# EFM32TG110_BreakoutBoard.net
KiCad netlist of a schematic drawn in EAGLE
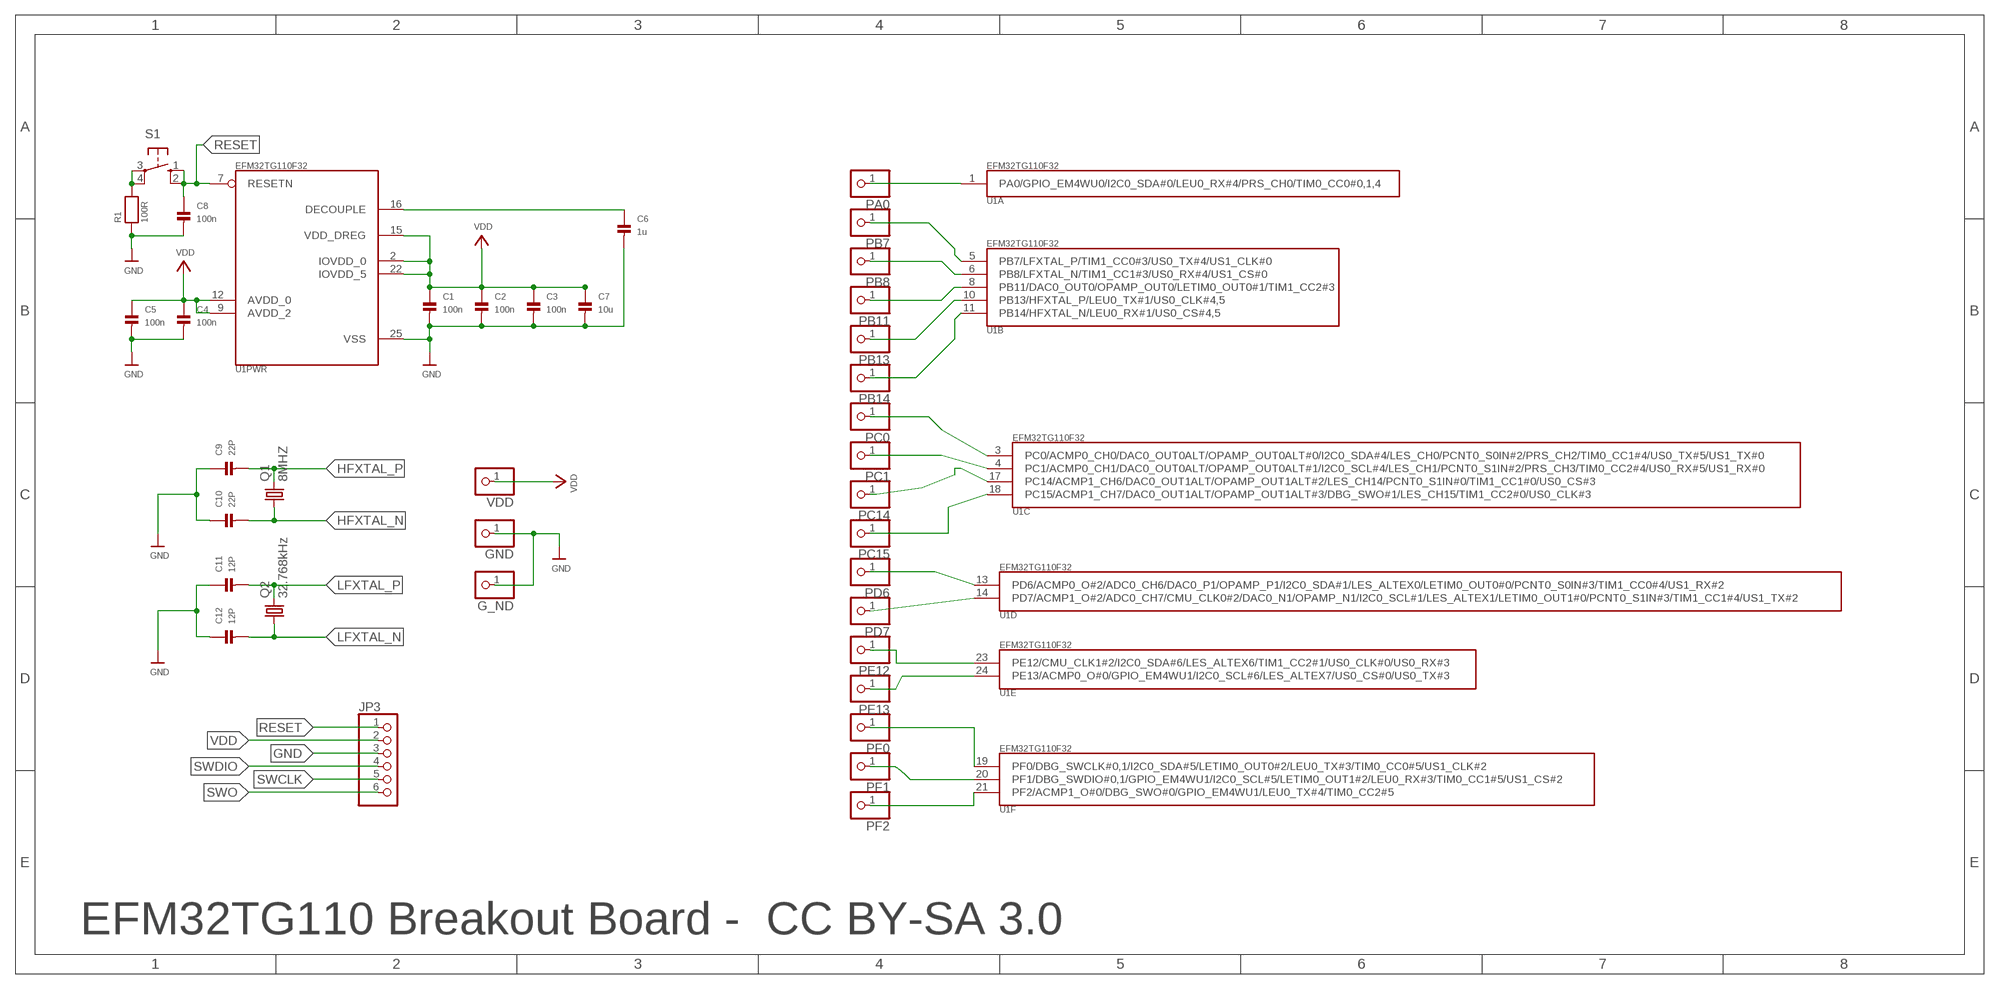
[diagram p0: schematic, sheet 1]

(export (version "E")
  (design (tool "Eeschema 10.0.6"))
  (components
    (comp (ref "C1")
      (value "100n")
      (footprint "eagle-import:0603")
      (libsource (lib "eagle-import") (part "CAP_CERAMIC0603"))
    )
    (comp (ref "C2")
      (value "100n")
      (footprint "eagle-import:0603")
      (libsource (lib "eagle-import") (part "CAP_CERAMIC0603"))
    )
    (comp (ref "C3")
      (value "100n")
      (footprint "eagle-import:0603")
      (libsource (lib "eagle-import") (part "CAP_CERAMIC0603"))
    )
    (comp (ref "C4")
      (value "100n")
      (footprint "eagle-import:0603")
      (libsource (lib "eagle-import") (part "CAP_CERAMIC0603"))
    )
    (comp (ref "C5")
      (value "100n")
      (footprint "eagle-import:0603")
      (libsource (lib "eagle-import") (part "CAP_CERAMIC0603"))
    )
    (comp (ref "C6")
      (value "1u")
      (footprint "eagle-import:0805")
      (libsource (lib "eagle-import") (part "CAP_CERAMIC0805"))
    )
    (comp (ref "C7")
      (value "10u")
      (footprint "eagle-import:0805")
      (libsource (lib "eagle-import") (part "CAP_CERAMIC0805"))
    )
    (comp (ref "C8")
      (value "100n")
      (footprint "eagle-import:0603")
      (libsource (lib "eagle-import") (part "CAP_CERAMIC0603"))
    )
    (comp (ref "C9")
      (value "22P")
      (footprint "eagle-import:0603")
      (libsource (lib "eagle-import") (part "CAP_CERAMIC0603"))
    )
    (comp (ref "C10")
      (value "22P")
      (footprint "eagle-import:0603")
      (libsource (lib "eagle-import") (part "CAP_CERAMIC0603"))
    )
    (comp (ref "C11")
      (value "12P")
      (footprint "eagle-import:0603")
      (libsource (lib "eagle-import") (part "CAP_CERAMIC0603"))
    )
    (comp (ref "C12")
      (value "12P")
      (footprint "eagle-import:0603")
      (libsource (lib "eagle-import") (part "CAP_CERAMIC0603"))
    )
    (comp (ref "GND")
      (value "HEADER-1X1ROUND")
      (footprint "eagle-import:1X01_ROUND")
      (libsource (lib "eagle-import") (part "HEADER-1X1ROUND"))
    )
    (comp (ref "G_ND")
      (value "HEADER-1X1ROUND")
      (footprint "eagle-import:1X01_ROUND")
      (libsource (lib "eagle-import") (part "HEADER-1X1ROUND"))
    )
    (comp (ref "JP3")
      (value "HEADER-1X6")
      (footprint "eagle-import:1X06_OVAL")
      (libsource (lib "eagle-import") (part "HEADER-1X6"))
    )
    (comp (ref "PA0")
      (value "HEADER-1X1ROUND")
      (footprint "eagle-import:1X01_ROUND")
      (libsource (lib "eagle-import") (part "HEADER-1X1ROUND"))
    )
    (comp (ref "PB7")
      (value "HEADER-1X1ROUND")
      (footprint "eagle-import:1X01_ROUND")
      (libsource (lib "eagle-import") (part "HEADER-1X1ROUND"))
    )
    (comp (ref "PB8")
      (value "HEADER-1X1ROUND")
      (footprint "eagle-import:1X01_ROUND")
      (libsource (lib "eagle-import") (part "HEADER-1X1ROUND"))
    )
    (comp (ref "PB11")
      (value "HEADER-1X1ROUND")
      (footprint "eagle-import:1X01_ROUND")
      (libsource (lib "eagle-import") (part "HEADER-1X1ROUND"))
    )
    (comp (ref "PB13")
      (value "HEADER-1X1ROUND")
      (footprint "eagle-import:1X01_ROUND")
      (libsource (lib "eagle-import") (part "HEADER-1X1ROUND"))
    )
    (comp (ref "PB14")
      (value "HEADER-1X1ROUND")
      (footprint "eagle-import:1X01_ROUND")
      (libsource (lib "eagle-import") (part "HEADER-1X1ROUND"))
    )
    (comp (ref "PC0")
      (value "HEADER-1X1ROUND")
      (footprint "eagle-import:1X01_ROUND")
      (libsource (lib "eagle-import") (part "HEADER-1X1ROUND"))
    )
    (comp (ref "PC1")
      (value "HEADER-1X1ROUND")
      (footprint "eagle-import:1X01_ROUND")
      (libsource (lib "eagle-import") (part "HEADER-1X1ROUND"))
    )
    (comp (ref "PC14")
      (value "HEADER-1X1ROUND")
      (footprint "eagle-import:1X01_ROUND")
      (libsource (lib "eagle-import") (part "HEADER-1X1ROUND"))
    )
    (comp (ref "PC15")
      (value "HEADER-1X1ROUND")
      (footprint "eagle-import:1X01_ROUND")
      (libsource (lib "eagle-import") (part "HEADER-1X1ROUND"))
    )
    (comp (ref "PD6")
      (value "HEADER-1X1ROUND")
      (footprint "eagle-import:1X01_ROUND")
      (libsource (lib "eagle-import") (part "HEADER-1X1ROUND"))
    )
    (comp (ref "PD7")
      (value "HEADER-1X1ROUND")
      (footprint "eagle-import:1X01_ROUND")
      (libsource (lib "eagle-import") (part "HEADER-1X1ROUND"))
    )
    (comp (ref "PE12")
      (value "HEADER-1X1ROUND")
      (footprint "eagle-import:1X01_ROUND")
      (libsource (lib "eagle-import") (part "HEADER-1X1ROUND"))
    )
    (comp (ref "PE13")
      (value "HEADER-1X1ROUND")
      (footprint "eagle-import:1X01_ROUND")
      (libsource (lib "eagle-import") (part "HEADER-1X1ROUND"))
    )
    (comp (ref "PF0")
      (value "HEADER-1X1ROUND")
      (footprint "eagle-import:1X01_ROUND")
      (libsource (lib "eagle-import") (part "HEADER-1X1ROUND"))
    )
    (comp (ref "PF1")
      (value "HEADER-1X1ROUND")
      (footprint "eagle-import:1X01_ROUND")
      (libsource (lib "eagle-import") (part "HEADER-1X1ROUND"))
    )
    (comp (ref "PF2")
      (value "HEADER-1X1ROUND")
      (footprint "eagle-import:1X01_ROUND")
      (libsource (lib "eagle-import") (part "HEADER-1X1ROUND"))
    )
    (comp (ref "Q1")
      (value "8MHZ")
      (footprint "eagle-import:HC49U70")
      (libsource (lib "eagle-import") (part "CRYSTALHC49U70"))
    )
    (comp (ref "Q2")
      (value "32.768kHz")
      (footprint "eagle-import:TC38H")
      (libsource (lib "eagle-import") (part "CRYSTALTC38H"))
    )
    (comp (ref "R1")
      (value "100R")
      (footprint "eagle-import:0603")
      (libsource (lib "eagle-import") (part "RESISTOR0603"))
    )
    (comp (ref "S1")
      (value "10-XX")
      (footprint "eagle-import:B3F-10XX")
      (fields (field (name "MPN") "B3F-1000"))
      (libsource (lib "eagle-import") (part "10-XX"))
    )
    (comp (ref "U1")
      (value "EFM32TG110F32")
      (footprint "eagle-import:QFN24")
      (libsource (lib "eagle-import") (part "EFM32TG110F32"))
    )
    (comp (ref "VDD")
      (value "HEADER-1X1ROUND")
      (footprint "eagle-import:1X01_ROUND")
      (libsource (lib "eagle-import") (part "HEADER-1X1ROUND"))
    )
  )
  (nets
    (net (code "1") (name "GND") (class "Default")
      (node (ref "C1") (pin "2") (pinfunction "P$2_2") (pintype "passive"))
      (node (ref "C10") (pin "1") (pinfunction "P$1_1") (pintype "passive"))
      (node (ref "C11") (pin "1") (pinfunction "P$1_1") (pintype "passive"))
      (node (ref "C12") (pin "1") (pinfunction "P$1_1") (pintype "passive"))
      (node (ref "C2") (pin "2") (pinfunction "P$2_2") (pintype "passive"))
      (node (ref "C3") (pin "2") (pinfunction "P$2_2") (pintype "passive"))
      (node (ref "C4") (pin "2") (pinfunction "P$2_2") (pintype "passive"))
      (node (ref "C5") (pin "2") (pinfunction "P$2_2") (pintype "passive"))
      (node (ref "C6") (pin "2") (pinfunction "P$2_2") (pintype "passive"))
      (node (ref "C7") (pin "2") (pinfunction "P$2_2") (pintype "passive"))
      (node (ref "C8") (pin "2") (pinfunction "P$2_2") (pintype "passive"))
      (node (ref "C9") (pin "1") (pinfunction "P$1_1") (pintype "passive"))
      (node (ref "GND") (pin "1") (pinfunction "1_1") (pintype "passive"))
      (node (ref "G_ND") (pin "1") (pinfunction "1_1") (pintype "passive"))
      (node (ref "JP3") (pin "3") (pinfunction "3_3") (pintype "passive"))
      (node (ref "R1") (pin "1") (pinfunction "1_1") (pintype "passive"))
      (node (ref "U1") (pin "25") (pinfunction "VSS_25") (pintype "power_in"))
    )
    (net (code "2") (name "HFXTAL_N") (class "Default")
      (node (ref "C10") (pin "2") (pinfunction "P$2_2") (pintype "passive"))
      (node (ref "PB14") (pin "1") (pinfunction "1_1") (pintype "passive"))
      (node (ref "Q1") (pin "1") (pinfunction "1_1") (pintype "passive"))
      (node (ref "U1") (pin "11") (pinfunction "PB14/HFXTAL_N/LEU0_RX#1/US0_CS#4,5_11") (pintype "bidirectional"))
    )
    (net (code "3") (name "HFXTAL_P") (class "Default")
      (node (ref "C9") (pin "2") (pinfunction "P$2_2") (pintype "passive"))
      (node (ref "PB13") (pin "1") (pinfunction "1_1") (pintype "passive"))
      (node (ref "Q1") (pin "2") (pinfunction "2_2") (pintype "passive"))
      (node (ref "U1") (pin "10") (pinfunction "PB13/HFXTAL_P/LEU0_TX#1/US0_CLK#4,5_10") (pintype "bidirectional"))
    )
    (net (code "4") (name "LFXTAL_N") (class "Default")
      (node (ref "C12") (pin "2") (pinfunction "P$2_2") (pintype "passive"))
      (node (ref "PB8") (pin "1") (pinfunction "1_1") (pintype "passive"))
      (node (ref "Q2") (pin "1") (pinfunction "1_1") (pintype "passive"))
      (node (ref "U1") (pin "6") (pinfunction "PB8/LFXTAL_N/TIM1_CC1#3/US0_RX#4/US1_CS#0_6") (pintype "bidirectional"))
    )
    (net (code "5") (name "LFXTAL_P") (class "Default")
      (node (ref "C11") (pin "2") (pinfunction "P$2_2") (pintype "passive"))
      (node (ref "PB7") (pin "1") (pinfunction "1_1") (pintype "passive"))
      (node (ref "Q2") (pin "2") (pinfunction "2_2") (pintype "passive"))
      (node (ref "U1") (pin "5") (pinfunction "PB7/LFXTAL_P/TIM1_CC0#3/US0_TX#4/US1_CLK#0_5") (pintype "bidirectional"))
    )
    (net (code "6") (name "Net-(C6-P$1)") (class "Default")
      (node (ref "C6") (pin "1") (pinfunction "P$1_1") (pintype "passive"))
      (node (ref "U1") (pin "16") (pinfunction "DECOUPLE_16") (pintype "power_in"))
    )
    (net (code "7") (name "Net-(S1-P)") (class "Default")
      (node (ref "R1") (pin "2") (pinfunction "2_2") (pintype "passive"))
      (node (ref "S1") (pin "3") (pinfunction "P_3") (pintype "passive"))
      (node (ref "S1") (pin "4") (pinfunction "P1_4") (pintype "passive"))
    )
    (net (code "8") (name "Net-(U1A-PA0{slash}GPIO_EM4WU0{slash}I2C0_SDA#0{slash}LEU0_RX#4{slash}PRS_CH0{slash}TIM0_CC0#0,1,4)") (class "Default")
      (node (ref "PA0") (pin "1") (pinfunction "1_1") (pintype "passive"))
      (node (ref "U1") (pin "1") (pinfunction "PA0/GPIO_EM4WU0/I2C0_SDA#0/LEU0_RX#4/PRS_CH0/TIM0_CC0#0,1,4_1") (pintype "bidirectional"))
    )
    (net (code "9") (name "Net-(U1B-PB11{slash}DAC0_OUT0{slash}OPAMP_OUT0{slash}LETIM0_OUT0#1{slash}TIM1_CC2#3)") (class "Default")
      (node (ref "PB11") (pin "1") (pinfunction "1_1") (pintype "passive"))
      (node (ref "U1") (pin "8") (pinfunction "PB11/DAC0_OUT0/OPAMP_OUT0/LETIM0_OUT0#1/TIM1_CC2#3_8") (pintype "bidirectional"))
    )
    (net (code "10") (name "Net-(U1C-PC0{slash}ACMP0_CH0{slash}DAC0_OUT0ALT{slash}OPAMP_OUT0ALT#0{slash}I2C0_SDA#4{slash}LES_CH0{slash}PCNT0_S0IN#2{slash}PRS_CH2{slash}TIM0_CC1#4{slash}US0_TX#5{slash}US1_TX#0)") (class "Default")
      (node (ref "PC0") (pin "1") (pinfunction "1_1") (pintype "passive"))
      (node (ref "U1") (pin "3") (pinfunction "PC0/ACMP0_CH0/DAC0_OUT0ALT/OPAMP_OUT0ALT#0/I2C0_SDA#4/LES_CH0/PCNT0_S0IN#2/PRS_CH2/TIM0_CC1#4/US0_TX#5/US1_TX#0_3") (pintype "bidirectional"))
    )
    (net (code "11") (name "Net-(U1C-PC1{slash}ACMP0_CH1{slash}DAC0_OUT0ALT{slash}OPAMP_OUT0ALT#1{slash}I2C0_SCL#4{slash}LES_CH1{slash}PCNT0_S1IN#2{slash}PRS_CH3{slash}TIM0_CC2#4{slash}US0_RX#5{slash}US1_RX#0)") (class "Default")
      (node (ref "PC1") (pin "1") (pinfunction "1_1") (pintype "passive"))
      (node (ref "U1") (pin "4") (pinfunction "PC1/ACMP0_CH1/DAC0_OUT0ALT/OPAMP_OUT0ALT#1/I2C0_SCL#4/LES_CH1/PCNT0_S1IN#2/PRS_CH3/TIM0_CC2#4/US0_RX#5/US1_RX#0_4") (pintype "bidirectional"))
    )
    (net (code "12") (name "Net-(U1C-PC14{slash}ACMP1_CH6{slash}DAC0_OUT1ALT{slash}OPAMP_OUT1ALT#2{slash}LES_CH14{slash}PCNT0_S1IN#0{slash}TIM1_CC1#0{slash}US0_CS#3)") (class "Default")
      (node (ref "PC14") (pin "1") (pinfunction "1_1") (pintype "passive"))
      (node (ref "U1") (pin "17") (pinfunction "PC14/ACMP1_CH6/DAC0_OUT1ALT/OPAMP_OUT1ALT#2/LES_CH14/PCNT0_S1IN#0/TIM1_CC1#0/US0_CS#3_17") (pintype "bidirectional"))
    )
    (net (code "13") (name "Net-(U1C-PC15{slash}ACMP1_CH7{slash}DAC0_OUT1ALT{slash}OPAMP_OUT1ALT#3{slash}DBG_SWO#1{slash}LES_CH15{slash}TIM1_CC2#0{slash}US0_CLK#3)") (class "Default")
      (node (ref "PC15") (pin "1") (pinfunction "1_1") (pintype "passive"))
      (node (ref "U1") (pin "18") (pinfunction "PC15/ACMP1_CH7/DAC0_OUT1ALT/OPAMP_OUT1ALT#3/DBG_SWO#1/LES_CH15/TIM1_CC2#0/US0_CLK#3_18") (pintype "bidirectional"))
    )
    (net (code "14") (name "Net-(U1D-PD6{slash}ACMP0_O#2{slash}ADC0_CH6{slash}DAC0_P1{slash}OPAMP_P1{slash}I2C0_SDA#1{slash}LES_ALTEX0{slash}LETIM0_OUT0#0{slash}PCNT0_S0IN#3{slash}TIM1_CC0#4{slash}US1_RX#2)") (class "Default")
      (node (ref "PD6") (pin "1") (pinfunction "1_1") (pintype "passive"))
      (node (ref "U1") (pin "13") (pinfunction "PD6/ACMP0_O#2/ADC0_CH6/DAC0_P1/OPAMP_P1/I2C0_SDA#1/LES_ALTEX0/LETIM0_OUT0#0/PCNT0_S0IN#3/TIM1_CC0#4/US1_RX#2_13") (pintype "bidirectional"))
    )
    (net (code "15") (name "Net-(U1D-PD7{slash}ACMP1_O#2{slash}ADC0_CH7{slash}CMU_CLK0#2{slash}DAC0_N1{slash}OPAMP_N1{slash}I2C0_SCL#1{slash}LES_ALTEX1{slash}LETIM0_OUT1#0{slash}PCNT0_S1IN#3{slash}TIM1_CC1#4{slash}US1_TX#2)") (class "Default")
      (node (ref "PD7") (pin "1") (pinfunction "1_1") (pintype "passive"))
      (node (ref "U1") (pin "14") (pinfunction "PD7/ACMP1_O#2/ADC0_CH7/CMU_CLK0#2/DAC0_N1/OPAMP_N1/I2C0_SCL#1/LES_ALTEX1/LETIM0_OUT1#0/PCNT0_S1IN#3/TIM1_CC1#4/US1_TX#2_14") (pintype "bidirectional"))
    )
    (net (code "16") (name "Net-(U1E-PE12{slash}CMU_CLK1#2{slash}I2C0_SDA#6{slash}LES_ALTEX6{slash}TIM1_CC2#1{slash}US0_CLK#0{slash}US0_RX#3)") (class "Default")
      (node (ref "PE12") (pin "1") (pinfunction "1_1") (pintype "passive"))
      (node (ref "U1") (pin "23") (pinfunction "PE12/CMU_CLK1#2/I2C0_SDA#6/LES_ALTEX6/TIM1_CC2#1/US0_CLK#0/US0_RX#3_23") (pintype "bidirectional"))
    )
    (net (code "17") (name "Net-(U1E-PE13{slash}ACMP0_O#0{slash}GPIO_EM4WU1{slash}I2C0_SCL#6{slash}LES_ALTEX7{slash}US0_CS#0{slash}US0_TX#3)") (class "Default")
      (node (ref "PE13") (pin "1") (pinfunction "1_1") (pintype "passive"))
      (node (ref "U1") (pin "24") (pinfunction "PE13/ACMP0_O#0/GPIO_EM4WU1/I2C0_SCL#6/LES_ALTEX7/US0_CS#0/US0_TX#3_24") (pintype "bidirectional"))
    )
    (net (code "18") (name "RESET") (class "Default")
      (node (ref "C8") (pin "1") (pinfunction "P$1_1") (pintype "passive"))
      (node (ref "JP3") (pin "1") (pinfunction "1_1") (pintype "passive"))
      (node (ref "S1") (pin "1") (pinfunction "S_1") (pintype "passive"))
      (node (ref "S1") (pin "2") (pinfunction "S1_2") (pintype "passive"))
      (node (ref "U1") (pin "7") (pinfunction "RESETN_7") (pintype "passive"))
    )
    (net (code "19") (name "SWCLK") (class "Default")
      (node (ref "JP3") (pin "5") (pinfunction "5_5") (pintype "passive"))
      (node (ref "PF0") (pin "1") (pinfunction "1_1") (pintype "passive"))
      (node (ref "U1") (pin "19") (pinfunction "PF0/DBG_SWCLK#0,1/I2C0_SDA#5/LETIM0_OUT0#2/LEU0_TX#3/TIM0_CC0#5/US1_CLK#2_19") (pintype "bidirectional"))
    )
    (net (code "20") (name "SWDIO") (class "Default")
      (node (ref "JP3") (pin "4") (pinfunction "4_4") (pintype "passive"))
      (node (ref "PF1") (pin "1") (pinfunction "1_1") (pintype "passive"))
      (node (ref "U1") (pin "20") (pinfunction "PF1/DBG_SWDIO#0,1/GPIO_EM4WU1/I2C0_SCL#5/LETIM0_OUT1#2/LEU0_RX#3/TIM0_CC1#5/US1_CS#2_20") (pintype "bidirectional"))
    )
    (net (code "21") (name "SWO") (class "Default")
      (node (ref "JP3") (pin "6") (pinfunction "6_6") (pintype "passive"))
      (node (ref "PF2") (pin "1") (pinfunction "1_1") (pintype "passive"))
      (node (ref "U1") (pin "21") (pinfunction "PF2/ACMP1_O#0/DBG_SWO#0/GPIO_EM4WU1/LEU0_TX#4/TIM0_CC2#5_21") (pintype "bidirectional"))
    )
    (net (code "22") (name "VDD") (class "Default")
      (node (ref "C1") (pin "1") (pinfunction "P$1_1") (pintype "passive"))
      (node (ref "C2") (pin "1") (pinfunction "P$1_1") (pintype "passive"))
      (node (ref "C3") (pin "1") (pinfunction "P$1_1") (pintype "passive"))
      (node (ref "C4") (pin "1") (pinfunction "P$1_1") (pintype "passive"))
      (node (ref "C5") (pin "1") (pinfunction "P$1_1") (pintype "passive"))
      (node (ref "C7") (pin "1") (pinfunction "P$1_1") (pintype "passive"))
      (node (ref "JP3") (pin "2") (pinfunction "2_2") (pintype "passive"))
      (node (ref "U1") (pin "12") (pinfunction "AVDD_0_12") (pintype "power_in"))
      (node (ref "U1") (pin "15") (pinfunction "VDD_DREG_15") (pintype "power_in"))
      (node (ref "U1") (pin "2") (pinfunction "IOVDD_0_2") (pintype "power_in"))
      (node (ref "U1") (pin "22") (pinfunction "IOVDD_5_22") (pintype "power_in"))
      (node (ref "U1") (pin "9") (pinfunction "AVDD_2_9") (pintype "power_in"))
      (node (ref "VDD") (pin "1") (pinfunction "1_1") (pintype "passive"))
    )
  )
)
